# 04-CTRL2-ps2-blueretro.net
KiCad netlist of a schematic drawn in Altium Designer
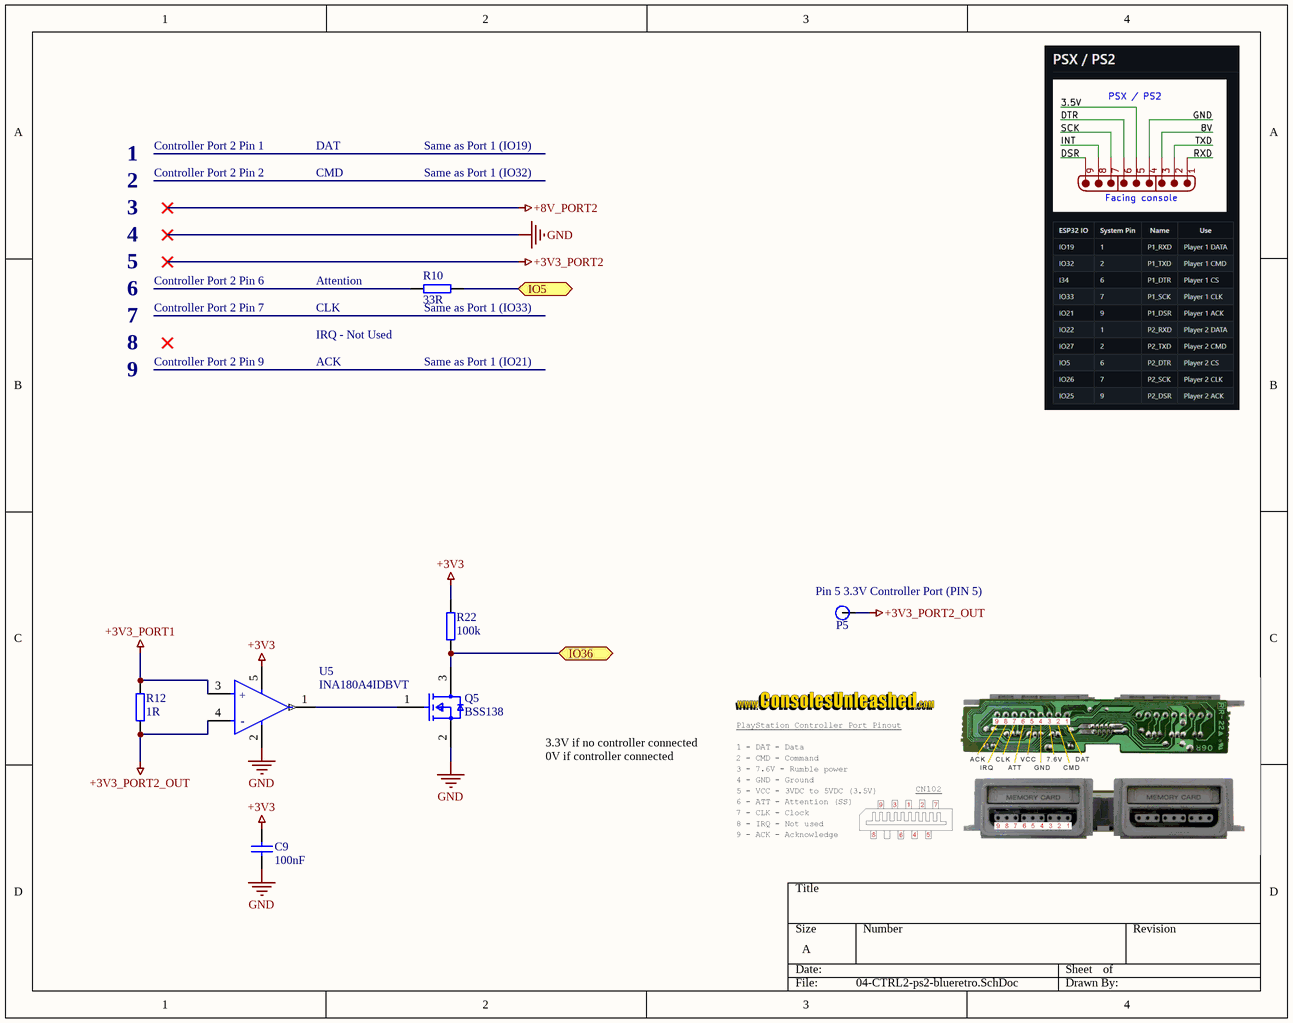
[diagram p0: 04-CTRL2-ps2-blueretro.SchDoc]

(export (version "E")
  (design (tool "Eeschema 10.0.6"))
  (components
    (comp (ref "C9")
      (value "100nF")
      (footprint "res_0402")
      (fields (field (name "Comment") "cap_0402"))
      (libsource (lib "mycomponents") (part "cap_0402"))
    )
    (comp (ref "P5")
      (value "Solder_Contact_2mm")
      (footprint "SINGLE_SOLDER_CON")
      (libsource (lib "mycomponents") (part "Solder_Contact_2mm"))
    )
    (comp (ref "Q5")
      (value "BSS138")
      (footprint "FP-318-08-IPC_B")
      (description "MOSFET N-CH 50V 220MA SOT-23")
      (libsource (lib "Altium Content Vault") (part "3b9c635fedb024a5347a57b145af9cc"))
    )
    (comp (ref "R10")
      (value "33R")
      (footprint "res_0402")
      (fields (field (name "Comment") "res_0402"))
      (libsource (lib "mycomponents") (part "res_0402"))
    )
    (comp (ref "R12")
      (value "1R")
      (footprint "res_0402")
      (fields (field (name "Comment") "res_0402"))
      (libsource (lib "mycomponents") (part "res_0402"))
    )
    (comp (ref "R22")
      (value "100k")
      (footprint "res_0603")
      (fields (field (name "Comment") "res_0603"))
      (libsource (lib "mycomponents") (part "res_0603"))
    )
    (comp (ref "U5")
      (value "INA180A4IDBVT")
      (footprint "FP-DBV0005A-MFG")
      (description "IC CURR SENSE 1 CIRCUIT SOT23-5")
      (fields
        (field (name "OCTOPART") "https://octopart.com/ina180a4idbvt-texas+instruments-81856280")
        (field (name "MANUFACTURER") "Texas Instruments")
      )
      (libsource (lib "Altium Content Vault") (part "0a55cf1a948ad01a3239aec1b7efad0"))
    )
  )
  (nets
    (net (code "1") (name "+3V3") (class "Default")
      (node (ref "C9") (pin "1") (pinfunction "1_1") (pintype "passive"))
      (node (ref "R22") (pin "2") (pinfunction "2_2") (pintype "passive"))
      (node (ref "U5") (pin "5") (pinfunction "VS_5") (pintype "power_in"))
    )
    (net (code "2") (name "+3V3_PORT1") (class "Default")
      (node (ref "R12") (pin "1") (pinfunction "1_1") (pintype "passive"))
      (node (ref "U5") (pin "3") (pinfunction "IN+_3") (pintype "tri_state"))
    )
    (net (code "4") (name "+3V3_PORT2_OUT") (class "Default")
      (node (ref "P5") (pin "1") (pinfunction "1_1") (pintype "passive"))
      (node (ref "R12") (pin "2") (pinfunction "2_2") (pintype "passive"))
      (node (ref "U5") (pin "4") (pinfunction "IN-_4") (pintype "tri_state"))
    )
    (net (code "6") (name "/IO5") (class "Default")
      (node (ref "R10") (pin "1") (pinfunction "1_1") (pintype "passive"))
    )
    (net (code "7") (name "/IO36") (class "Default")
      (node (ref "Q5") (pin "3") (pinfunction "D_3") (pintype "passive"))
      (node (ref "R22") (pin "1") (pinfunction "1_1") (pintype "passive"))
    )
    (net (code "8") (name "GND") (class "Default")
      (node (ref "C9") (pin "2") (pinfunction "2_2") (pintype "passive"))
      (node (ref "Q5") (pin "2") (pinfunction "S_2") (pintype "passive"))
      (node (ref "U5") (pin "2") (pinfunction "GND_2") (pintype "power_in"))
    )
    (net (code "9") (name "Net-(Q5-G)") (class "Default")
      (node (ref "Q5") (pin "1") (pinfunction "G_1") (pintype "passive"))
      (node (ref "U5") (pin "1") (pinfunction "OUT_1") (pintype "output"))
    )
    (net (code "10") (name "unconnected-(R10-Pad2)") (class "Default")
      (node (ref "R10") (pin "2") (pinfunction "2_2") (pintype "passive"))
    )
  )
)
